# ActiTouch.net
KiCad netlist of a schematic drawn in Altium Designer
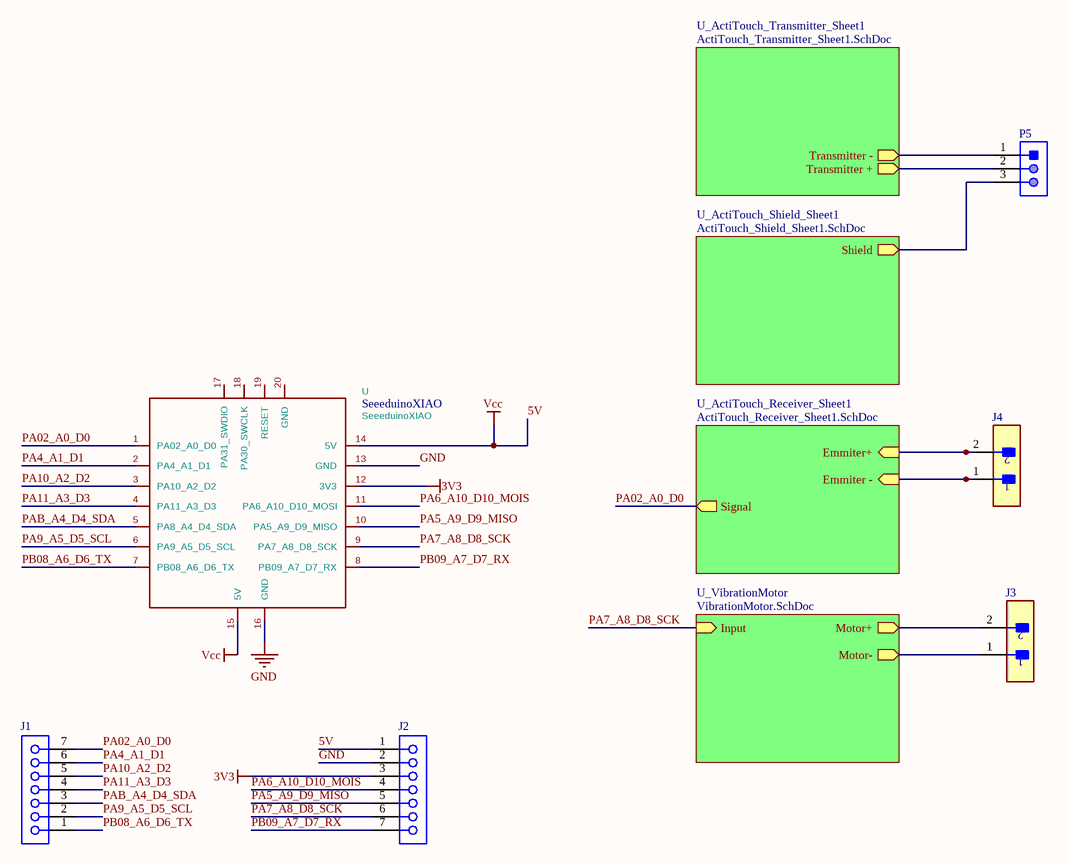
[diagram p0: ActiTouch.SchDoc]

(export (version "E")
  (design (tool "Eeschema 10.0.6"))
  (components
    (comp (ref "J1")
      (value "SSQ-107-01-G-S")
      (footprint "SMTC-SSQ-107-01-X-S")
      (description "SQ Post Socket, Through-hole, Vertical, -55 to 125 degC, 2.54 mm Pitch, 7-Pin, Female, RoHS")
      (fields (field (name "MANUFACTURER") "Samtec"))
      (libsource (lib "Altium Content Vault") (part "SMTC-SSQ-107-01-X-S"))
    )
    (comp (ref "J2")
      (value "SSQ-107-01-G-S")
      (footprint "SMTC-SSQ-107-01-X-S")
      (description "SQ Post Socket, Through-hole, Vertical, -55 to 125 degC, 2.54 mm Pitch, 7-Pin, Female, RoHS")
      (fields (field (name "MANUFACTURER") "Samtec"))
      (libsource (lib "Altium Content Vault") (part "SMTC-SSQ-107-01-X-S"))
    )
    (comp (ref "J3")
      (value "GRPB021VWVN-RC")
      (footprint "FP-GRPB021VWVN-RC-MFG")
      (description "CONN HEADER VERT 2POS 1.27MM")
      (libsource (lib "Altium Content Vault") (part "3bc925449376181038e59eaffc5286c"))
    )
    (comp (ref "J4")
      (value "GRPB021VWVN-RC")
      (footprint "FP-GRPB021VWVN-RC-MFG")
      (description "CONN HEADER VERT 2POS 1.27MM")
      (libsource (lib "Altium Content Vault") (part "3bc925449376181038e59eaffc5286c"))
    )
    (comp (ref "P5")
      (value "GRPB031VWVN-RC")
      (footprint "SLIN-GRPB031VWVN-RC_V")
      (fields (field (name "MANUFACTURER") "Sullins"))
      (libsource (lib "Altium Content Vault") (part "CN-1P-M-R3"))
    )
    (comp (ref "U")
      (value "SeeeduinoXIAO")
      (footprint "Seeeduino XIAO-MOUDLE14P-2.54-21X17.8MM")
      (fields (field (name "ALTIUM_VALUE") "SeeeduinoXIAO"))
      (libsource (lib "Seeeduino XIAO") (part "SeeeduinoXIAO"))
    )
  )
  (nets
    (net (code "1") (name "/Emmiter -") (class "Default")
      (node (ref "J4") (pin "1") (pinfunction "1_1") (pintype "passive"))
    )
    (net (code "2") (name "/Emmiter+") (class "Default")
      (node (ref "J4") (pin "2") (pinfunction "2_2") (pintype "passive"))
    )
    (net (code "3") (name "/Motor+") (class "Default")
      (node (ref "J3") (pin "2") (pinfunction "2_2") (pintype "passive"))
    )
    (net (code "4") (name "/Motor-") (class "Default")
      (node (ref "J3") (pin "1") (pinfunction "1_1") (pintype "passive"))
    )
    (net (code "5") (name "/PA02_A0_D0") (class "Default")
      (node (ref "J1") (pin "7") (pinfunction "7_7") (pintype "passive"))
      (node (ref "U") (pin "1") (pinfunction "PA02_A0_D0_1") (pintype "passive"))
    )
    (net (code "6") (name "/PA4_A1_D1") (class "Default")
      (node (ref "J1") (pin "6") (pinfunction "6_6") (pintype "passive"))
      (node (ref "U") (pin "2") (pinfunction "PA4_A1_D1_2") (pintype "passive"))
    )
    (net (code "7") (name "/PA5_A9_D9_MISO") (class "Default")
      (node (ref "J2") (pin "5") (pinfunction "5_5") (pintype "passive"))
      (node (ref "U") (pin "10") (pinfunction "PA5_A9_D9_MISO_10") (pintype "passive"))
    )
    (net (code "8") (name "/PA6_A10_D10_MOIS") (class "Default")
      (node (ref "J2") (pin "4") (pinfunction "4_4") (pintype "passive"))
      (node (ref "U") (pin "11") (pinfunction "PA6_A10_D10_MOSI_11") (pintype "passive"))
    )
    (net (code "9") (name "/PA7_A8_D8_SCK") (class "Default")
      (node (ref "J2") (pin "6") (pinfunction "6_6") (pintype "passive"))
      (node (ref "U") (pin "9") (pinfunction "PA7_A8_D8_SCK_9") (pintype "passive"))
    )
    (net (code "10") (name "/PA9_A5_D5_SCL") (class "Default")
      (node (ref "J1") (pin "2") (pinfunction "2_2") (pintype "passive"))
      (node (ref "U") (pin "6") (pinfunction "PA9_A5_D5_SCL_6") (pintype "passive"))
    )
    (net (code "11") (name "/PA10_A2_D2") (class "Default")
      (node (ref "J1") (pin "5") (pinfunction "5_5") (pintype "passive"))
      (node (ref "U") (pin "3") (pinfunction "PA10_A2_D2_3") (pintype "passive"))
    )
    (net (code "12") (name "/PA11_A3_D3") (class "Default")
      (node (ref "J1") (pin "4") (pinfunction "4_4") (pintype "passive"))
      (node (ref "U") (pin "4") (pinfunction "PA11_A3_D3_4") (pintype "passive"))
    )
    (net (code "13") (name "/PAB_A4_D4_SDA") (class "Default")
      (node (ref "J1") (pin "3") (pinfunction "3_3") (pintype "passive"))
      (node (ref "U") (pin "5") (pinfunction "PA8_A4_D4_SDA_5") (pintype "passive"))
    )
    (net (code "14") (name "/PB08_A6_D6_TX") (class "Default")
      (node (ref "J1") (pin "1") (pinfunction "1_1") (pintype "passive"))
      (node (ref "U") (pin "7") (pinfunction "PB08_A6_D6_TX_7") (pintype "passive"))
    )
    (net (code "15") (name "/PB09_A7_D7_RX") (class "Default")
      (node (ref "J2") (pin "7") (pinfunction "7_7") (pintype "passive"))
      (node (ref "U") (pin "8") (pinfunction "PB09_A7_D7_RX_8") (pintype "passive"))
    )
    (net (code "16") (name "/Shield") (class "Default")
      (node (ref "P5") (pin "3") (pinfunction "3_3") (pintype "passive"))
    )
    (net (code "17") (name "/Transmitter +") (class "Default")
      (node (ref "P5") (pin "2") (pinfunction "2_2") (pintype "passive"))
    )
    (net (code "18") (name "/Transmitter -") (class "Default")
      (node (ref "P5") (pin "1") (pinfunction "1_1") (pintype "passive"))
    )
    (net (code "19") (name "3V3") (class "Default")
      (node (ref "J2") (pin "3") (pinfunction "3_3") (pintype "passive"))
      (node (ref "U") (pin "12") (pinfunction "3V3_12") (pintype "passive"))
    )
    (net (code "20") (name "GND") (class "Default")
      (node (ref "J2") (pin "2") (pinfunction "2_2") (pintype "passive"))
      (node (ref "U") (pin "13") (pinfunction "GND_13") (pintype "passive"))
      (node (ref "U") (pin "16") (pinfunction "GND_16") (pintype "passive"))
    )
    (net (code "21") (name "Vcc") (class "Default")
      (node (ref "J2") (pin "1") (pinfunction "1_1") (pintype "passive"))
      (node (ref "U") (pin "14") (pinfunction "5V_14") (pintype "passive"))
      (node (ref "U") (pin "15") (pinfunction "5V_15") (pintype "passive"))
    )
    (net (code "22") (name "unconnected-(U-GND-Pad20)") (class "Default")
      (node (ref "U") (pin "20") (pinfunction "GND_20") (pintype "passive"))
    )
    (net (code "23") (name "unconnected-(U-PA30_SWCLK-Pad18)") (class "Default")
      (node (ref "U") (pin "18") (pinfunction "PA30_SWCLK_18") (pintype "passive"))
    )
    (net (code "24") (name "unconnected-(U-PA31_SWDIO-Pad17)") (class "Default")
      (node (ref "U") (pin "17") (pinfunction "PA31_SWDIO_17") (pintype "passive"))
    )
    (net (code "25") (name "unconnected-(U-RESET-Pad19)") (class "Default")
      (node (ref "U") (pin "19") (pinfunction "RESET_19") (pintype "passive"))
    )
  )
)
